# light_humid.net
KiCad netlist of a schematic drawn in Altium Designer
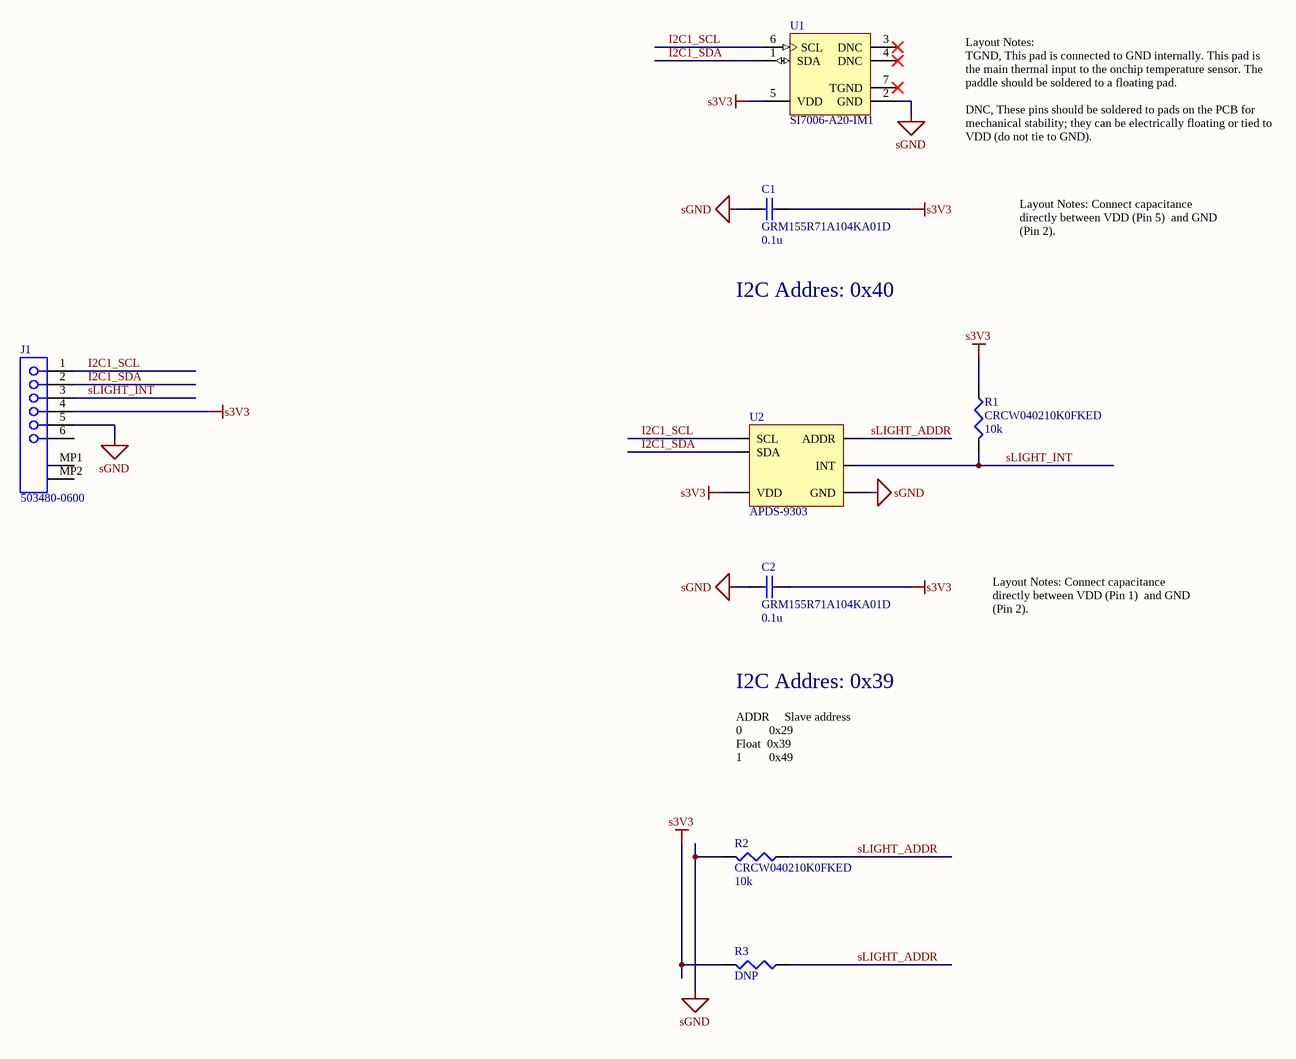
[diagram p0: light_humid.SchDoc]

(export (version "E")
  (design (tool "Eeschema 10.0.6"))
  (components
    (comp (ref "C1")
      (value "GRM155R71A104KA01D")
      (footprint "0402")
      (description "-55-125C, 1005, 10V, X7R, ±10%")
      (fields (field (name "ALTIUM_VALUE") "0.1u"))
      (libsource (lib "standard_capacitors") (part "GRM155R71AxxxKdddd"))
    )
    (comp (ref "C2")
      (value "GRM155R71A104KA01D")
      (footprint "0402")
      (description "-55-125C, 1005, 10V, X7R, ±10%")
      (fields (field (name "ALTIUM_VALUE") "0.1u"))
      (libsource (lib "standard_capacitors") (part "GRM155R71AxxxKdddd"))
    )
    (comp (ref "J1")
      (value "503480-0600")
      (footprint "MOLX-503480-0600")
      (fields (field (name "MANUFACTURER") "Molex"))
      (libsource (lib "Altium Content Vault") (part "MOLX-503480-0600"))
    )
    (comp (ref "R1")
      (value "CRCW040210K0FKED")
      (footprint "0402")
      (description "0.125W, -55-155C, 1005, 50V, ±1%")
      (fields (field (name "ALTIUM_VALUE") "10k"))
      (libsource (lib "standard_resistors") (part "CRCW0402xxxxFKED"))
    )
    (comp (ref "R2")
      (value "CRCW040210K0FKED")
      (footprint "0402")
      (description "0.125W, -55-155C, 1005, 50V, ±1%")
      (fields (field (name "ALTIUM_VALUE") "10k"))
      (libsource (lib "standard_resistors") (part "CRCW0402xxxxFKED"))
    )
    (comp (ref "R3")
      (value "DNP")
      (footprint "0402")
      (description "0.125W, -55-155C, 1005, 50V, ±1%")
      (libsource (lib "standard_resistors") (part "CRCW0402xxxxFKED"))
    )
    (comp (ref "U1")
      (value "SI7006-A20-IM1")
      (footprint "SLAB-DFN-6-1500X2400TP_V")
      (description "I2C Humidity and Temperature Sensor, 1.9 to 3.6 V, -40 to 125 degC, 6-Pin DFN, RoHS, Tube")
      (fields (field (name "MANUFACTURER") "Silicon Labs"))
      (libsource (lib "Altium Content Vault") (part "CMP-2000-07060-1"))
    )
    (comp (ref "U2") (value "APDS-9303") (footprint "APDS-9303") (libsource (lib "avago") (part "APDS-9303")))
  )
  (nets
    (net (code "1") (name "/I2C1_SCL") (class "Default")
      (node (ref "J1") (pin "1") (pinfunction "1_1") (pintype "passive"))
      (node (ref "U1") (pin "6") (pinfunction "SCL_6") (pintype "input"))
      (node (ref "U2") (pin "4") (pinfunction "SCL_4") (pintype "passive"))
    )
    (net (code "2") (name "/I2C1_SDA") (class "Default")
      (node (ref "J1") (pin "2") (pinfunction "2_2") (pintype "passive"))
      (node (ref "U1") (pin "1") (pinfunction "SDA_1") (pintype "bidirectional"))
      (node (ref "U2") (pin "5") (pinfunction "SDA_5") (pintype "passive"))
    )
    (net (code "3") (name "/sLIGHT_ADDR") (class "Default")
      (node (ref "R2") (pin "1") (pinfunction "1_1") (pintype "passive"))
      (node (ref "R3") (pin "1") (pinfunction "1_1") (pintype "passive"))
      (node (ref "U2") (pin "3") (pinfunction "ADDR_3") (pintype "passive"))
    )
    (net (code "4") (name "/sLIGHT_INT") (class "Default")
      (node (ref "J1") (pin "3") (pinfunction "3_3") (pintype "passive"))
      (node (ref "R1") (pin "2") (pinfunction "2_2") (pintype "passive"))
      (node (ref "U2") (pin "6") (pinfunction "INT_6") (pintype "passive"))
    )
    (net (code "5") (name "s3V3") (class "Default")
      (node (ref "C1") (pin "2") (pinfunction "2_2") (pintype "passive"))
      (node (ref "C2") (pin "2") (pinfunction "2_2") (pintype "passive"))
      (node (ref "J1") (pin "4") (pinfunction "4_4") (pintype "passive"))
      (node (ref "R1") (pin "1") (pinfunction "1_1") (pintype "passive"))
      (node (ref "R3") (pin "2") (pinfunction "2_2") (pintype "passive"))
      (node (ref "U1") (pin "5") (pinfunction "VDD_5") (pintype "power_in"))
      (node (ref "U2") (pin "1") (pinfunction "VDD_1") (pintype "passive"))
    )
    (net (code "6") (name "sGND") (class "Default")
      (node (ref "C1") (pin "1") (pinfunction "1_1") (pintype "passive"))
      (node (ref "C2") (pin "1") (pinfunction "1_1") (pintype "passive"))
      (node (ref "J1") (pin "5") (pinfunction "5_5") (pintype "passive"))
      (node (ref "R2") (pin "2") (pinfunction "2_2") (pintype "passive"))
      (node (ref "U1") (pin "2") (pinfunction "GND_2") (pintype "power_in"))
      (node (ref "U2") (pin "2") (pinfunction "GND_2") (pintype "passive"))
    )
    (net (code "7") (name "unconnected-(J1-Pad6)") (class "Default")
      (node (ref "J1") (pin "6") (pinfunction "6_6") (pintype "passive"))
    )
    (net (code "8") (name "unconnected-(J1-PadMP1)") (class "Default")
      (node (ref "J1") (pin "MP1") (pinfunction "MP1_MP1") (pintype "passive"))
    )
    (net (code "9") (name "unconnected-(J1-PadMP2)") (class "Default")
      (node (ref "J1") (pin "MP2") (pinfunction "MP2_MP2") (pintype "passive"))
    )
    (net (code "10") (name "unconnected-(U1-DNC-Pad3)") (class "Default")
      (node (ref "U1") (pin "3") (pinfunction "DNC_3") (pintype "passive+no_connect"))
    )
    (net (code "11") (name "unconnected-(U1-DNC-Pad4)") (class "Default")
      (node (ref "U1") (pin "4") (pinfunction "DNC_4") (pintype "passive+no_connect"))
    )
    (net (code "12") (name "unconnected-(U1-TGND-Pad7)") (class "Default")
      (node (ref "U1") (pin "7") (pinfunction "TGND_7") (pintype "power_in+no_connect"))
    )
  )
)
